# sparkfun-samd21-mini-breakout.net
KiCad netlist of a schematic drawn in Altium Designer
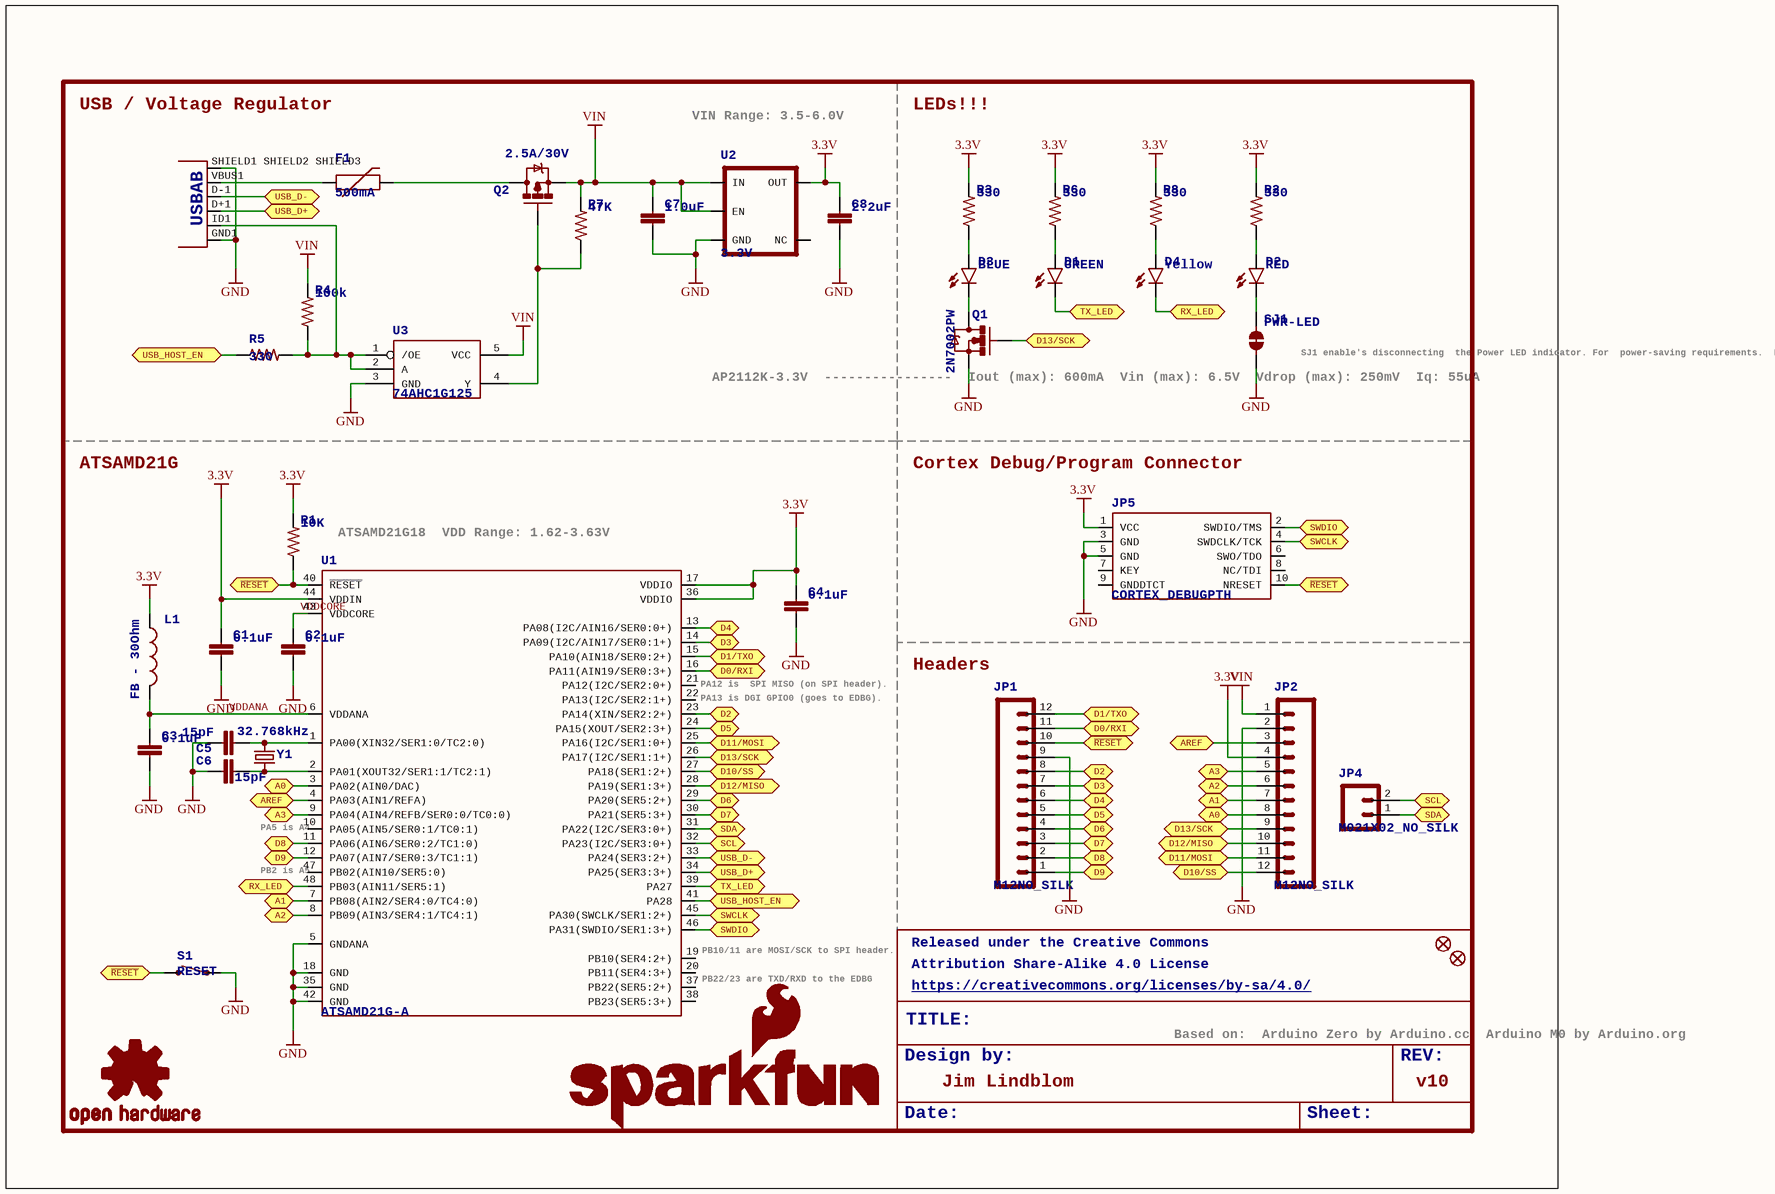
[diagram p0: sparkfun-samd21-mini-breakout.SchDoc]

(export (version "E")
  (design (tool "Eeschema 10.0.6"))
  (components
    (comp (ref "C1")
      (value "0.1uF")
      (footprint "0402-CAP")
      (libsource (lib "SparkFun-Capacitors") (part "0.1UF-16V(+-10%)(0402)"))
    )
    (comp (ref "C2")
      (value "0.1uF")
      (footprint "0402-CAP")
      (libsource (lib "SparkFun-Capacitors") (part "0.1UF-16V(+-10%)(0402)"))
    )
    (comp (ref "C3")
      (value "0.1uF")
      (footprint "0402-CAP")
      (libsource (lib "SparkFun-Capacitors") (part "0.1UF-16V(+-10%)(0402)"))
    )
    (comp (ref "C4")
      (value "0.1uF")
      (footprint "0402-CAP")
      (libsource (lib "") (part "0.1UF-16V(+-10%)(0402)_1"))
    )
    (comp (ref "C5")
      (value "15pF")
      (footprint "0402-CAP")
      (libsource (lib "") (part "15PF-50V(+-5%)(0402)_1"))
    )
    (comp (ref "C6")
      (value "15pF")
      (footprint "0402-CAP")
      (libsource (lib "samd21-temp") (part "15PF-50V(+-5%)(0402)"))
    )
    (comp (ref "C7")
      (value "1.0uF")
      (footprint "0805-CAP")
      (description "CAP-11625")
      (libsource (lib "SparkFun-Capacitors") (part "1.0UF-25V-+80/-20(0805){dblquote}"))
    )
    (comp (ref "C8")
      (value "2.2uF")
      (footprint "0603-CAP")
      (description "CAP-07888")
      (libsource (lib "SparkFun-Capacitors") (part "2.2UF-10V-20%(0603)"))
    )
    (comp (ref "D1")
      (value "GREEN")
      (footprint "LED-0603")
      (libsource (lib "SparkFun-LED") (part "LED-GREEN0603"))
    )
    (comp (ref "D2")
      (value "RED")
      (footprint "LED-0603")
      (libsource (lib "SparkFun-LED") (part "LED-RED0603"))
    )
    (comp (ref "D3")
      (value "BLUE")
      (footprint "LED-0603")
      (libsource (lib "SparkFun-LED") (part "LED-BLUE0603"))
    )
    (comp (ref "D4")
      (value "Yellow")
      (footprint "LED-0603")
      (libsource (lib "SparkFun-LED") (part "LED-YELLOW0603"))
    )
    (comp (ref "F1")
      (value "500mA")
      (footprint "PTC-1206")
      (description "Resettable Fuse PTCResettable Fuse. Spark Fun Electronics SKU : COM-08357")
      (libsource (lib "SparkFun-PowerIC") (part "PTCSMD"))
    )
    (comp (ref "FID1")
      (value "FIDUCIAL1X2")
      (footprint "FIDUCIAL-1X2")
      (description "Fiducial Alignment PointsVarious fiducial points for machine vision alignment.")
      (libsource (lib "SparkFun-Aesthetics") (part "FIDUCIAL1X2"))
    )
    (comp (ref "FID2")
      (value "FIDUCIAL1X2")
      (footprint "FIDUCIAL-1X2")
      (description "Fiducial Alignment PointsVarious fiducial points for machine vision alignment.")
      (libsource (lib "SparkFun-Aesthetics") (part "FIDUCIAL1X2"))
    )
    (comp (ref "JP1")
      (value "M12NO_SILK")
      (footprint "1X12_NO_SILK")
      (libsource (lib "SparkFun-Connectors") (part "M12NO_SILK"))
    )
    (comp (ref "JP2")
      (value "M12NO_SILK")
      (footprint "1X12_NO_SILK")
      (libsource (lib "SparkFun-Connectors") (part "M12NO_SILK"))
    )
    (comp (ref "JP3")
      (value "USB-ABCONN-11794")
      (footprint "USB-AB-MICRO-SMD_V03")
      (fields (field (name "USBAB") "USBAB"))
      (libsource (lib "SparkFun-Connectors") (part "USB-ABCONN-11794"))
    )
    (comp (ref "JP4")
      (value "M021X02_NO_SILK")
      (footprint "1X02_NO_SILK")
      (libsource (lib "SparkFun-Connectors") (part "M021X02_NO_SILK"))
    )
    (comp (ref "JP5")
      (value "CORTEX_DEBUGPTH")
      (footprint "2X5-PTH-1.27MM")
      (description "Cortex Debug Connector    Datasheet")
      (libsource (lib "samd21-temp") (part "CORTEX_DEBUGPTH"))
    )
    (comp (ref "L1")
      (value "FB - 30Ohm")
      (footprint "0603")
      (libsource (lib "SparkFun-Passives") (part "INDUCTOR0603"))
    )
    (comp (ref "LOGO1")
      (value "SFE_LOGO_FLAME.1_INCH")
      (footprint "SFE_LOGO_FLAME_.1")
      (libsource (lib "SparkFun-Aesthetics") (part "SFE_LOGO_FLAME.1_INCH"))
    )
    (comp (ref "LOGO2")
      (value "OSHW-LOGOS")
      (footprint "OSHW-LOGO-S")
      (libsource (lib "SparkFun-Aesthetics") (part "OSHW-LOGOS"))
    )
    (comp (ref "LOGO3")
      (value "SFE_LOGO_NAME_FLAME.1_INCH")
      (footprint "SFE_LOGO_NAME_FLAME_.1")
      (libsource (lib "SparkFun-Aesthetics") (part "SFE_LOGO_NAME_FLAME.1_INCH"))
    )
    (comp (ref "Q1")
      (value "2N7002PW")
      (footprint "SOT323")
      (libsource (lib "SparkFun-DiscreteSemi") (part "MOSFET-NCHANNEL2N7002PW"))
    )
    (comp (ref "Q2")
      (value "2.5A/30V")
      (footprint "SOT23-3")
      (libsource (lib "SparkFun-DiscreteSemi") (part "MOSFET-PCHANNELDMG2307L"))
    )
    (comp (ref "R1")
      (value "10K")
      (footprint "0603-RES")
      (description "RES-00824")
      (libsource (lib "SparkFun-Resistors") (part "10KOHM-1/10W-1%(0603)0603"))
    )
    (comp (ref "R2")
      (value "330")
      (footprint "0603-RES")
      (description "RES-00818")
      (libsource (lib "SparkFun-Resistors") (part "330OHM1/10W1%(0603)"))
    )
    (comp (ref "R3")
      (value "330")
      (footprint "0603-RES")
      (description "RES-00818")
      (libsource (lib "SparkFun-Resistors") (part "330OHM1/10W1%(0603)"))
    )
    (comp (ref "R4")
      (value "100k")
      (footprint "0603-RES")
      (description "RES-07828")
      (libsource (lib "SparkFun-Resistors") (part "100KOHM-1/10W-1%(0603)"))
    )
    (comp (ref "R5")
      (value "330")
      (footprint "0603-RES")
      (description "RES-00818")
      (libsource (lib "SparkFun-Resistors") (part "330OHM1/10W1%(0603)"))
    )
    (comp (ref "R6")
      (value "330")
      (footprint "0603-RES")
      (description "RES-00818")
      (libsource (lib "SparkFun-Resistors") (part "330OHM1/10W1%(0603)"))
    )
    (comp (ref "R7")
      (value "47K")
      (footprint "0603-RES")
      (description "RES-07871")
      (libsource (lib "SparkFun-Resistors") (part "47KOHM1/10W1%(0603)"))
    )
    (comp (ref "R8")
      (value "330")
      (footprint "0603-RES")
      (description "RES-00818")
      (libsource (lib "SparkFun-Resistors") (part "330OHM1/10W1%(0603)"))
    )
    (comp (ref "S1")
      (value "RESET")
      (footprint "TACTILE_SWITCH_SMD_4.6X2.8MM")
      (description "Various NO switches- pushbuttons, reed, etc")
      (libsource (lib "samd21-temp") (part "SWITCH-MOMENTARY-2SMD-4.6X2.8MM"))
    )
    (comp (ref "SJ1")
      (value "PWR-LED")
      (footprint "PAD-JUMPER-2-NC_BY_TRACE_NO_SILK")
      (libsource (lib "SparkFun-Passives") (part "JUMPER-PAD-2-NC_BY_TRACENO_SILK"))
    )
    (comp (ref "U1")
      (value "ATSAMD21G-A")
      (footprint "TQFP-48")
      (libsource (lib "samd21-temp") (part "ATSAMD21G-A"))
    )
    (comp (ref "U2")
      (value "3.3V")
      (footprint "SOT23-5")
      (libsource (lib "SparkFun-PowerIC") (part "V_REG_AP2112K-3.3V"))
    )
    (comp (ref "U3")
      (value "74AHC1G125")
      (footprint "SOT23-5")
      (description "Single bus buffer gate with 3-state output")
      (libsource (lib "SparkFun-DigitalIC") (part "74AHC1G125"))
    )
    (comp (ref "Y1")
      (value "32.768kHz")
      (footprint "CRYSTAL-SMD-3.2X1.5MM")
      (description "Various standard crystals. Proven footprints.")
      (libsource (lib "samd21-temp") (part "CRYSTAL3.2X1.5MM"))
    )
  )
  (nets
    (net (code "1") (name "/A0") (class "Default")
      (node (ref "JP2") (pin "8") (pinfunction "8_8") (pintype "passive"))
      (node (ref "U1") (pin "3") (pinfunction "PA02(AIN0/DAC)_3") (pintype "passive"))
    )
    (net (code "2") (name "/A1") (class "Default")
      (node (ref "JP2") (pin "7") (pinfunction "7_7") (pintype "passive"))
      (node (ref "U1") (pin "7") (pinfunction "PB08(AIN2/SER4:0/TC4:0)_7") (pintype "passive"))
    )
    (net (code "3") (name "/A2") (class "Default")
      (node (ref "JP2") (pin "6") (pinfunction "6_6") (pintype "passive"))
      (node (ref "U1") (pin "8") (pinfunction "PB09(AIN3/SER4:1/TC4:1)_8") (pintype "passive"))
    )
    (net (code "4") (name "/A3") (class "Default")
      (node (ref "JP2") (pin "5") (pinfunction "5_5") (pintype "passive"))
      (node (ref "U1") (pin "9") (pinfunction "PA04(AIN4/REFB/SER0:0/TC0:0)_9") (pintype "passive"))
    )
    (net (code "5") (name "/AREF") (class "Default")
      (node (ref "JP2") (pin "3") (pinfunction "3_3") (pintype "passive"))
      (node (ref "U1") (pin "4") (pinfunction "PA03(AIN1/REFA)_4") (pintype "passive"))
    )
    (net (code "6") (name "/D0{slash}RXI") (class "Default")
      (node (ref "JP1") (pin "11") (pinfunction "11_11") (pintype "passive"))
      (node (ref "U1") (pin "16") (pinfunction "PA11(AIN19/SER0:3+)_16") (pintype "passive"))
    )
    (net (code "7") (name "/D1{slash}TXO") (class "Default")
      (node (ref "JP1") (pin "12") (pinfunction "12_12") (pintype "passive"))
      (node (ref "U1") (pin "15") (pinfunction "PA10(AIN18/SER0:2+)_15") (pintype "passive"))
    )
    (net (code "8") (name "/D2") (class "Default")
      (node (ref "JP1") (pin "8") (pinfunction "8_8") (pintype "passive"))
      (node (ref "U1") (pin "23") (pinfunction "PA14(XIN/SER2:2+)_23") (pintype "passive"))
    )
    (net (code "9") (name "/D3") (class "Default")
      (node (ref "JP1") (pin "7") (pinfunction "7_7") (pintype "passive"))
      (node (ref "U1") (pin "14") (pinfunction "PA09(I2C/AIN17/SER0:1+)_14") (pintype "passive"))
    )
    (net (code "10") (name "/D4") (class "Default")
      (node (ref "JP1") (pin "6") (pinfunction "6_6") (pintype "passive"))
      (node (ref "U1") (pin "13") (pinfunction "PA08(I2C/AIN16/SER0:0+)_13") (pintype "passive"))
    )
    (net (code "11") (name "/D5") (class "Default")
      (node (ref "JP1") (pin "5") (pinfunction "5_5") (pintype "passive"))
      (node (ref "U1") (pin "24") (pinfunction "PA15(XOUT/SER2:3+)_24") (pintype "passive"))
    )
    (net (code "12") (name "/D6") (class "Default")
      (node (ref "JP1") (pin "4") (pinfunction "4_4") (pintype "passive"))
      (node (ref "U1") (pin "29") (pinfunction "PA20(SER5:2+)_29") (pintype "passive"))
    )
    (net (code "13") (name "/D7") (class "Default")
      (node (ref "JP1") (pin "3") (pinfunction "3_3") (pintype "passive"))
      (node (ref "U1") (pin "30") (pinfunction "PA21(SER5:3+)_30") (pintype "passive"))
    )
    (net (code "14") (name "/D8") (class "Default")
      (node (ref "JP1") (pin "2") (pinfunction "2_2") (pintype "passive"))
      (node (ref "U1") (pin "11") (pinfunction "PA06(AIN6/SER0:2/TC1:0)_11") (pintype "passive"))
    )
    (net (code "15") (name "/D9") (class "Default")
      (node (ref "JP1") (pin "1") (pinfunction "1_1") (pintype "passive"))
      (node (ref "U1") (pin "12") (pinfunction "PA07(AIN7/SER0:3/TC1:1)_12") (pintype "passive"))
    )
    (net (code "16") (name "/D10{slash}SS") (class "Default")
      (node (ref "JP2") (pin "12") (pinfunction "12_12") (pintype "passive"))
      (node (ref "U1") (pin "27") (pinfunction "PA18(SER1:2+)_27") (pintype "passive"))
    )
    (net (code "17") (name "/D11{slash}MOSI") (class "Default")
      (node (ref "JP2") (pin "11") (pinfunction "11_11") (pintype "passive"))
      (node (ref "U1") (pin "25") (pinfunction "PA16(I2C/SER1:0+)_25") (pintype "passive"))
    )
    (net (code "18") (name "/D12{slash}MISO") (class "Default")
      (node (ref "JP2") (pin "10") (pinfunction "10_10") (pintype "passive"))
      (node (ref "U1") (pin "28") (pinfunction "PA19(SER1:3+)_28") (pintype "passive"))
    )
    (net (code "19") (name "/D13{slash}SCK") (class "Default")
      (node (ref "JP2") (pin "9") (pinfunction "9_9") (pintype "passive"))
      (node (ref "Q1") (pin "1") (pinfunction "G_1") (pintype "passive"))
      (node (ref "U1") (pin "26") (pinfunction "PA17(I2C/SER1:1+)_26") (pintype "passive"))
    )
    (net (code "20") (name "/RX_LED") (class "Default")
      (node (ref "D4") (pin "C") (pinfunction "C_C") (pintype "passive"))
      (node (ref "U1") (pin "48") (pinfunction "PB03(AIN11/SER5:1)_48") (pintype "passive"))
    )
    (net (code "21") (name "/SCL") (class "Default")
      (node (ref "JP4") (pin "2") (pinfunction "2_2") (pintype "passive"))
      (node (ref "U1") (pin "32") (pinfunction "PA23(I2C/SER3:0+)_32") (pintype "passive"))
    )
    (net (code "22") (name "/SDA") (class "Default")
      (node (ref "JP4") (pin "1") (pinfunction "1_1") (pintype "passive"))
      (node (ref "U1") (pin "31") (pinfunction "PA22(I2C/SER3:0+)_31") (pintype "passive"))
    )
    (net (code "23") (name "/SWCLK") (class "Default")
      (node (ref "JP5") (pin "4") (pinfunction "SWDCLK/TCK_4") (pintype "passive"))
      (node (ref "U1") (pin "45") (pinfunction "PA30(SWCLK/SER1:2+)_45") (pintype "passive"))
    )
    (net (code "24") (name "/SWDIO") (class "Default")
      (node (ref "JP5") (pin "2") (pinfunction "SWDIO/TMS_2") (pintype "passive"))
      (node (ref "U1") (pin "46") (pinfunction "PA31(SWDIO/SER1:3+)_46") (pintype "passive"))
    )
    (net (code "25") (name "/TX_LED") (class "Default")
      (node (ref "D1") (pin "C") (pinfunction "C_C") (pintype "passive"))
      (node (ref "U1") (pin "39") (pinfunction "PA27_39") (pintype "passive"))
    )
    (net (code "26") (name "/USB_D+") (class "Default")
      (node (ref "JP3") (pin "D+1") (pinfunction "D+_D+1") (pintype "passive"))
      (node (ref "U1") (pin "34") (pinfunction "PA25(SER3:3+)_34") (pintype "passive"))
    )
    (net (code "27") (name "/USB_D-") (class "Default")
      (node (ref "JP3") (pin "D-1") (pinfunction "D-_D-1") (pintype "passive"))
      (node (ref "U1") (pin "33") (pinfunction "PA24(SER3:2+)_33") (pintype "passive"))
    )
    (net (code "28") (name "/USB_HOST_EN") (class "Default")
      (node (ref "R5") (pin "1") (pinfunction "1_1") (pintype "passive"))
      (node (ref "U1") (pin "41") (pinfunction "PA28_41") (pintype "passive"))
    )
    (net (code "29") (name "/VDDANA") (class "Default")
      (node (ref "C3") (pin "1") (pinfunction "1_1") (pintype "passive"))
      (node (ref "L1") (pin "2") (pinfunction "2_2") (pintype "passive"))
      (node (ref "U1") (pin "6") (pinfunction "VDDANA_6") (pintype "passive"))
    )
    (net (code "30") (name "/VDDCORE") (class "Default")
      (node (ref "C2") (pin "1") (pinfunction "1_1") (pintype "passive"))
      (node (ref "U1") (pin "43") (pinfunction "VDDCORE_43") (pintype "passive"))
    )
    (net (code "31") (name "/~{RESET}") (class "Default")
      (node (ref "JP1") (pin "10") (pinfunction "10_10") (pintype "passive"))
      (node (ref "JP5") (pin "10") (pinfunction "NRESET_10") (pintype "passive"))
      (node (ref "R1") (pin "1") (pinfunction "1_1") (pintype "passive"))
      (node (ref "S1") (pin "3_4") (pinfunction "2_3_4") (pintype "passive"))
      (node (ref "U1") (pin "40") (pinfunction "~{RESET}_40") (pintype "passive"))
    )
    (net (code "32") (name "3.3V") (class "Default")
      (node (ref "C1") (pin "1") (pinfunction "1_1") (pintype "passive"))
      (node (ref "C4") (pin "1") (pinfunction "1_1") (pintype "passive"))
      (node (ref "C8") (pin "1") (pinfunction "1_1") (pintype "passive"))
      (node (ref "JP2") (pin "4") (pinfunction "4_4") (pintype "passive"))
      (node (ref "JP5") (pin "1") (pinfunction "VCC_1") (pintype "passive"))
      (node (ref "L1") (pin "1") (pinfunction "1_1") (pintype "passive"))
      (node (ref "R1") (pin "2") (pinfunction "2_2") (pintype "passive"))
      (node (ref "R2") (pin "2") (pinfunction "2_2") (pintype "passive"))
      (node (ref "R3") (pin "2") (pinfunction "2_2") (pintype "passive"))
      (node (ref "R6") (pin "2") (pinfunction "2_2") (pintype "passive"))
      (node (ref "R8") (pin "2") (pinfunction "2_2") (pintype "passive"))
      (node (ref "U1") (pin "17") (pinfunction "VDDIO_17") (pintype "passive"))
      (node (ref "U1") (pin "36") (pinfunction "VDDIO_36") (pintype "passive"))
      (node (ref "U1") (pin "44") (pinfunction "VDDIN_44") (pintype "passive"))
      (node (ref "U2") (pin "5") (pinfunction "OUT_5") (pintype "passive"))
    )
    (net (code "33") (name "GND") (class "Default")
      (node (ref "C1") (pin "2") (pinfunction "2_2") (pintype "passive"))
      (node (ref "C2") (pin "2") (pinfunction "2_2") (pintype "passive"))
      (node (ref "C3") (pin "2") (pinfunction "2_2") (pintype "passive"))
      (node (ref "C4") (pin "2") (pinfunction "2_2") (pintype "passive"))
      (node (ref "C5") (pin "1") (pinfunction "1_1") (pintype "passive"))
      (node (ref "C6") (pin "2") (pinfunction "2_2") (pintype "passive"))
      (node (ref "C7") (pin "2") (pinfunction "2_2") (pintype "passive"))
      (node (ref "C8") (pin "2") (pinfunction "2_2") (pintype "passive"))
      (node (ref "JP1") (pin "9") (pinfunction "9_9") (pintype "passive"))
      (node (ref "JP2") (pin "2") (pinfunction "2_2") (pintype "passive"))
      (node (ref "JP3") (pin "GND1") (pinfunction "GND_GND1") (pintype "passive"))
      (node (ref "JP3") (pin "SHIELD1_SHIELD2_SHIELD3") (pinfunction "SHIELD_SHIELD1_SHIELD2_SHIELD3") (pintype "passive"))
      (node (ref "JP5") (pin "3") (pinfunction "GND_3") (pintype "passive"))
      (node (ref "JP5") (pin "5") (pinfunction "GND_5") (pintype "passive"))
      (node (ref "Q1") (pin "2") (pinfunction "S_2") (pintype "passive"))
      (node (ref "S1") (pin "1_2") (pinfunction "1_1_2") (pintype "passive"))
      (node (ref "SJ1") (pin "1") (pinfunction "1_1") (pintype "passive"))
      (node (ref "U1") (pin "18") (pinfunction "GND_18") (pintype "passive"))
      (node (ref "U1") (pin "35") (pinfunction "GND_35") (pintype "passive"))
      (node (ref "U1") (pin "42") (pinfunction "GND_42") (pintype "passive"))
      (node (ref "U1") (pin "5") (pinfunction "GNDANA_5") (pintype "passive"))
      (node (ref "U2") (pin "2") (pinfunction "GND_2") (pintype "passive"))
      (node (ref "U3") (pin "3") (pinfunction "GND_3") (pintype "passive"))
    )
    (net (code "34") (name "Net-(D1-PadA)") (class "Default")
      (node (ref "D1") (pin "A") (pinfunction "A_A") (pintype "passive"))
      (node (ref "R6") (pin "1") (pinfunction "1_1") (pintype "passive"))
    )
    (net (code "35") (name "Net-(D2-PadA)") (class "Default")
      (node (ref "D2") (pin "A") (pinfunction "A_A") (pintype "passive"))
      (node (ref "R2") (pin "1") (pinfunction "1_1") (pintype "passive"))
    )
    (net (code "36") (name "Net-(D2-PadC)") (class "Default")
      (node (ref "D2") (pin "C") (pinfunction "C_C") (pintype "passive"))
      (node (ref "SJ1") (pin "2") (pinfunction "2_2") (pintype "passive"))
    )
    (net (code "37") (name "Net-(D3-PadA)") (class "Default")
      (node (ref "D3") (pin "A") (pinfunction "A_A") (pintype "passive"))
      (node (ref "R3") (pin "1") (pinfunction "1_1") (pintype "passive"))
    )
    (net (code "38") (name "Net-(D4-PadA)") (class "Default")
      (node (ref "D4") (pin "A") (pinfunction "A_A") (pintype "passive"))
      (node (ref "R8") (pin "1") (pinfunction "1_1") (pintype "passive"))
    )
    (net (code "39") (name "Net-(JP3-USBID)") (class "Default")
      (node (ref "JP3") (pin "ID1") (pinfunction "USBID_ID1") (pintype "passive"))
      (node (ref "R4") (pin "1") (pinfunction "1_1") (pintype "passive"))
      (node (ref "R5") (pin "2") (pinfunction "2_2") (pintype "passive"))
      (node (ref "U3") (pin "1") (pinfunction "/OE_1") (pintype "passive"))
      (node (ref "U3") (pin "2") (pinfunction "A_2") (pintype "passive"))
    )
    (net (code "40") (name "Net-(JP3-VBUS)") (class "Default")
      (node (ref "F1") (pin "1") (pinfunction "1_1") (pintype "passive"))
      (node (ref "JP3") (pin "VBUS1") (pinfunction "VBUS_VBUS1") (pintype "passive"))
    )
    (net (code "41") (name "Net-(Q1-D)") (class "Default")
      (node (ref "D3") (pin "C") (pinfunction "C_C") (pintype "passive"))
      (node (ref "Q1") (pin "3") (pinfunction "D_3") (pintype "passive"))
    )
    (net (code "42") (name "Net-(Q2-D)") (class "Default")
      (node (ref "F1") (pin "2") (pinfunction "2_2") (pintype "passive"))
      (node (ref "Q2") (pin "3") (pinfunction "D_3") (pintype "passive"))
    )
    (net (code "43") (name "Net-(Q2-G)") (class "Default")
      (node (ref "Q2") (pin "1") (pinfunction "G_1") (pintype "passive"))
      (node (ref "R7") (pin "1") (pinfunction "1_1") (pintype "passive"))
      (node (ref "U3") (pin "4") (pinfunction "Y_4") (pintype "passive"))
    )
    (net (code "44") (name "Net-(U1-PA00(XIN32{slash}SER1:0{slash}TC2:0))") (class "Default")
      (node (ref "C5") (pin "2") (pinfunction "2_2") (pintype "passive"))
      (node (ref "U1") (pin "1") (pinfunction "PA00(XIN32/SER1:0/TC2:0)_1") (pintype "passive"))
      (node (ref "Y1") (pin "P$2") (pinfunction "2_P$2") (pintype "passive"))
    )
    (net (code "45") (name "Net-(U1-PA01(XOUT32{slash}SER1:1{slash}TC2:1))") (class "Default")
      (node (ref "C6") (pin "1") (pinfunction "1_1") (pintype "passive"))
      (node (ref "U1") (pin "2") (pinfunction "PA01(XOUT32/SER1:1/TC2:1)_2") (pintype "passive"))
      (node (ref "Y1") (pin "P$1") (pinfunction "1_P$1") (pintype "passive"))
    )
    (net (code "46") (name "VIN") (class "Default")
      (node (ref "C7") (pin "1") (pinfunction "1_1") (pintype "passive"))
      (node (ref "JP2") (pin "1") (pinfunction "1_1") (pintype "passive"))
      (node (ref "Q2") (pin "2") (pinfunction "S_2") (pintype "passive"))
      (node (ref "R4") (pin "2") (pinfunction "2_2") (pintype "passive"))
      (node (ref "R7") (pin "2") (pinfunction "2_2") (pintype "passive"))
      (node (ref "U2") (pin "1") (pinfunction "IN_1") (pintype "passive"))
      (node (ref "U2") (pin "3") (pinfunction "EN_3") (pintype "passive"))
      (node (ref "U3") (pin "5") (pinfunction "VCC_5") (pintype "passive"))
    )
    (net (code "47") (name "unconnected-(JP5-GNDDTCT-Pad9)") (class "Default")
      (node (ref "JP5") (pin "9") (pinfunction "GNDDTCT_9") (pintype "passive"))
    )
    (net (code "48") (name "unconnected-(JP5-KEY-Pad7)") (class "Default")
      (node (ref "JP5") (pin "7") (pinfunction "KEY_7") (pintype "passive"))
    )
    (net (code "49") (name "unconnected-(JP5-NC{slash}TDI-Pad8)") (class "Default")
      (node (ref "JP5") (pin "8") (pinfunction "NC/TDI_8") (pintype "passive"))
    )
    (net (code "50") (name "unconnected-(JP5-SWO{slash}TDO-Pad6)") (class "Default")
      (node (ref "JP5") (pin "6") (pinfunction "SWO/TDO_6") (pintype "passive"))
    )
    (net (code "51") (name "unconnected-(U1-PA05(AIN5{slash}SER0:1{slash}TC0:1)-Pad10)") (class "Default")
      (node (ref "U1") (pin "10") (pinfunction "PA05(AIN5/SER0:1/TC0:1)_10") (pintype "passive"))
    )
    (net (code "52") (name "unconnected-(U1-PA12(I2C{slash}SER2:0+)-Pad21)") (class "Default")
      (node (ref "U1") (pin "21") (pinfunction "PA12(I2C/SER2:0+)_21") (pintype "passive"))
    )
    (net (code "53") (name "unconnected-(U1-PA13(I2C{slash}SER2:1+)-Pad22)") (class "Default")
      (node (ref "U1") (pin "22") (pinfunction "PA13(I2C/SER2:1+)_22") (pintype "passive"))
    )
    (net (code "54") (name "unconnected-(U1-PB02(AIN10{slash}SER5:0)-Pad47)") (class "Default")
      (node (ref "U1") (pin "47") (pinfunction "PB02(AIN10/SER5:0)_47") (pintype "passive"))
    )
    (net (code "55") (name "unconnected-(U1-PB10(SER4:2+)-Pad19)") (class "Default")
      (node (ref "U1") (pin "19") (pinfunction "PB10(SER4:2+)_19") (pintype "passive"))
    )
    (net (code "56") (name "unconnected-(U1-PB11(SER4:3+)-Pad20)") (class "Default")
      (node (ref "U1") (pin "20") (pinfunction "PB11(SER4:3+)_20") (pintype "passive"))
    )
    (net (code "57") (name "unconnected-(U1-PB22(SER5:2+)-Pad37)") (class "Default")
      (node (ref "U1") (pin "37") (pinfunction "PB22(SER5:2+)_37") (pintype "passive"))
    )
    (net (code "58") (name "unconnected-(U1-PB23(SER5:3+)-Pad38)") (class "Default")
      (node (ref "U1") (pin "38") (pinfunction "PB23(SER5:3+)_38") (pintype "passive"))
    )
    (net (code "59") (name "unconnected-(U2-NC-Pad4)") (class "Default")
      (node (ref "U2") (pin "4") (pinfunction "NC_4") (pintype "passive"))
    )
  )
)
